# avr_gamepanel.net
KiCad netlist of a schematic drawn in EAGLE
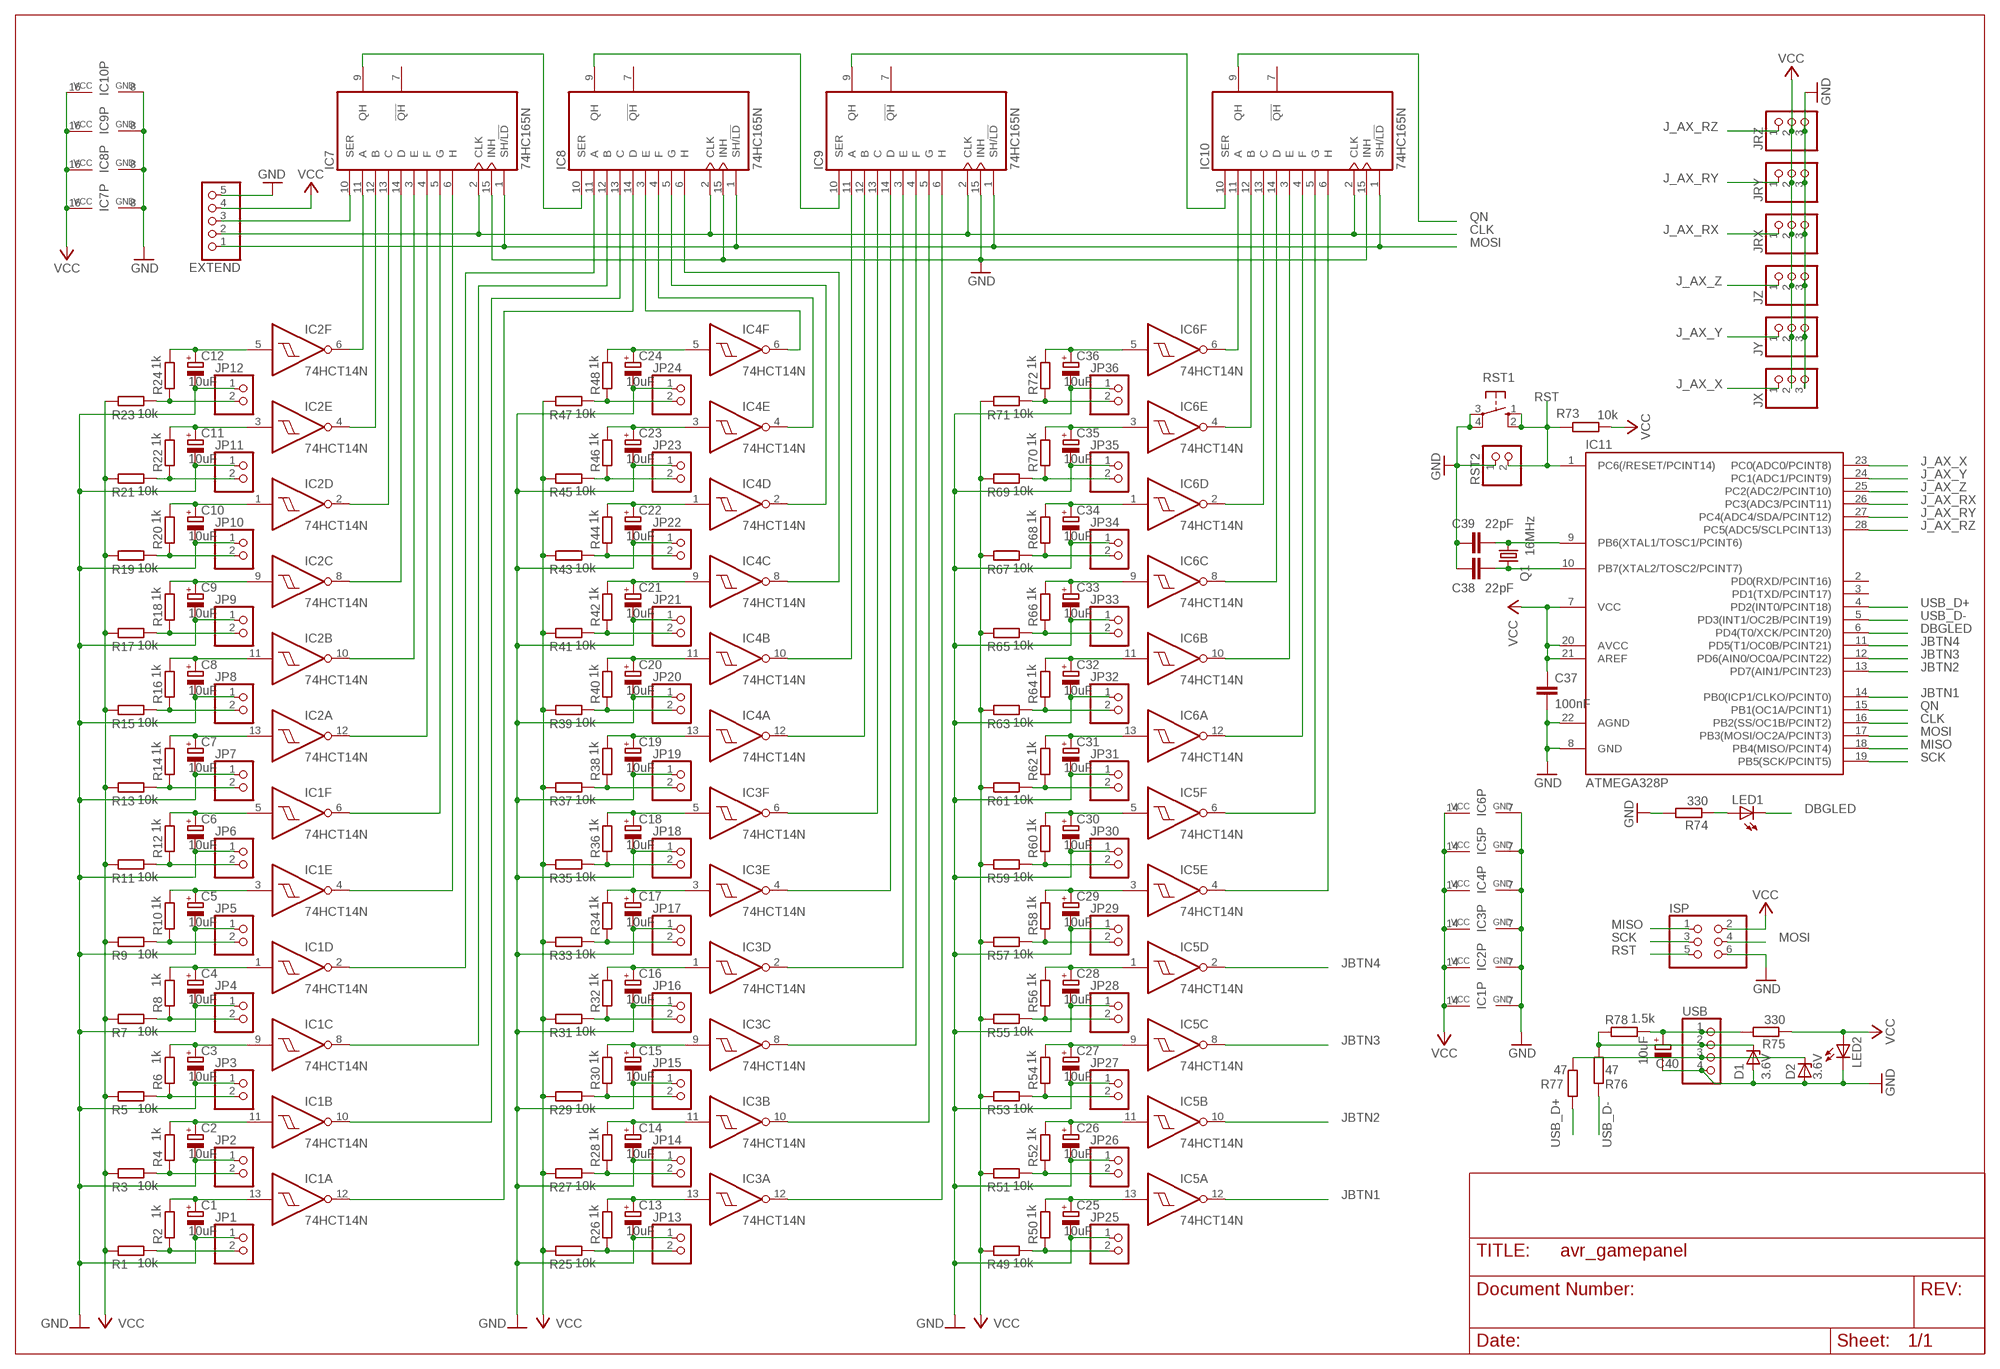
[diagram p0: schematic, sheet 1]

(export (version "E")
  (design (tool "Eeschema 10.0.6"))
  (components
    (comp (ref "C1")
      (value "10uF")
      (footprint "eagle-import:E2-5")
      (libsource (lib "eagle-import") (part "CPOL-EUE2-5"))
    )
    (comp (ref "C2")
      (value "10uF")
      (footprint "eagle-import:E2-5")
      (libsource (lib "eagle-import") (part "CPOL-EUE2-5"))
    )
    (comp (ref "C3")
      (value "10uF")
      (footprint "eagle-import:E2-5")
      (libsource (lib "eagle-import") (part "CPOL-EUE2-5"))
    )
    (comp (ref "C4")
      (value "10uF")
      (footprint "eagle-import:E2-5")
      (libsource (lib "eagle-import") (part "CPOL-EUE2-5"))
    )
    (comp (ref "C5")
      (value "10uF")
      (footprint "eagle-import:E2-5")
      (libsource (lib "eagle-import") (part "CPOL-EUE2-5"))
    )
    (comp (ref "C6")
      (value "10uF")
      (footprint "eagle-import:E2-5")
      (libsource (lib "eagle-import") (part "CPOL-EUE2-5"))
    )
    (comp (ref "C7")
      (value "10uF")
      (footprint "eagle-import:E2-5")
      (libsource (lib "eagle-import") (part "CPOL-EUE2-5"))
    )
    (comp (ref "C8")
      (value "10uF")
      (footprint "eagle-import:E2-5")
      (libsource (lib "eagle-import") (part "CPOL-EUE2-5"))
    )
    (comp (ref "C9")
      (value "10uF")
      (footprint "eagle-import:E2-5")
      (libsource (lib "eagle-import") (part "CPOL-EUE2-5"))
    )
    (comp (ref "C10")
      (value "10uF")
      (footprint "eagle-import:E2-5")
      (libsource (lib "eagle-import") (part "CPOL-EUE2-5"))
    )
    (comp (ref "C11")
      (value "10uF")
      (footprint "eagle-import:E2-5")
      (libsource (lib "eagle-import") (part "CPOL-EUE2-5"))
    )
    (comp (ref "C12")
      (value "10uF")
      (footprint "eagle-import:E2-5")
      (libsource (lib "eagle-import") (part "CPOL-EUE2-5"))
    )
    (comp (ref "C13")
      (value "10uF")
      (footprint "eagle-import:E2-5")
      (libsource (lib "eagle-import") (part "CPOL-EUE2-5"))
    )
    (comp (ref "C14")
      (value "10uF")
      (footprint "eagle-import:E2-5")
      (libsource (lib "eagle-import") (part "CPOL-EUE2-5"))
    )
    (comp (ref "C15")
      (value "10uF")
      (footprint "eagle-import:E2-5")
      (libsource (lib "eagle-import") (part "CPOL-EUE2-5"))
    )
    (comp (ref "C16")
      (value "10uF")
      (footprint "eagle-import:E2-5")
      (libsource (lib "eagle-import") (part "CPOL-EUE2-5"))
    )
    (comp (ref "C17")
      (value "10uF")
      (footprint "eagle-import:E2-5")
      (libsource (lib "eagle-import") (part "CPOL-EUE2-5"))
    )
    (comp (ref "C18")
      (value "10uF")
      (footprint "eagle-import:E2-5")
      (libsource (lib "eagle-import") (part "CPOL-EUE2-5"))
    )
    (comp (ref "C19")
      (value "10uF")
      (footprint "eagle-import:E2-5")
      (libsource (lib "eagle-import") (part "CPOL-EUE2-5"))
    )
    (comp (ref "C20")
      (value "10uF")
      (footprint "eagle-import:E2-5")
      (libsource (lib "eagle-import") (part "CPOL-EUE2-5"))
    )
    (comp (ref "C21")
      (value "10uF")
      (footprint "eagle-import:E2-5")
      (libsource (lib "eagle-import") (part "CPOL-EUE2-5"))
    )
    (comp (ref "C22")
      (value "10uF")
      (footprint "eagle-import:E2-5")
      (libsource (lib "eagle-import") (part "CPOL-EUE2-5"))
    )
    (comp (ref "C23")
      (value "10uF")
      (footprint "eagle-import:E2-5")
      (libsource (lib "eagle-import") (part "CPOL-EUE2-5"))
    )
    (comp (ref "C24")
      (value "10uF")
      (footprint "eagle-import:E2-5")
      (libsource (lib "eagle-import") (part "CPOL-EUE2-5"))
    )
    (comp (ref "C25")
      (value "10uF")
      (footprint "eagle-import:E2-5")
      (libsource (lib "eagle-import") (part "CPOL-EUE2-5"))
    )
    (comp (ref "C26")
      (value "10uF")
      (footprint "eagle-import:E2-5")
      (libsource (lib "eagle-import") (part "CPOL-EUE2-5"))
    )
    (comp (ref "C27")
      (value "10uF")
      (footprint "eagle-import:E2-5")
      (libsource (lib "eagle-import") (part "CPOL-EUE2-5"))
    )
    (comp (ref "C28")
      (value "10uF")
      (footprint "eagle-import:E2-5")
      (libsource (lib "eagle-import") (part "CPOL-EUE2-5"))
    )
    (comp (ref "C29")
      (value "10uF")
      (footprint "eagle-import:E2-5")
      (libsource (lib "eagle-import") (part "CPOL-EUE2-5"))
    )
    (comp (ref "C30")
      (value "10uF")
      (footprint "eagle-import:E2-5")
      (libsource (lib "eagle-import") (part "CPOL-EUE2-5"))
    )
    (comp (ref "C31")
      (value "10uF")
      (footprint "eagle-import:E2-5")
      (libsource (lib "eagle-import") (part "CPOL-EUE2-5"))
    )
    (comp (ref "C32")
      (value "10uF")
      (footprint "eagle-import:E2-5")
      (libsource (lib "eagle-import") (part "CPOL-EUE2-5"))
    )
    (comp (ref "C33")
      (value "10uF")
      (footprint "eagle-import:E2-5")
      (libsource (lib "eagle-import") (part "CPOL-EUE2-5"))
    )
    (comp (ref "C34")
      (value "10uF")
      (footprint "eagle-import:E2-5")
      (libsource (lib "eagle-import") (part "CPOL-EUE2-5"))
    )
    (comp (ref "C35")
      (value "10uF")
      (footprint "eagle-import:E2-5")
      (libsource (lib "eagle-import") (part "CPOL-EUE2-5"))
    )
    (comp (ref "C36")
      (value "10uF")
      (footprint "eagle-import:E2-5")
      (libsource (lib "eagle-import") (part "CPOL-EUE2-5"))
    )
    (comp (ref "C37")
      (value "100nF")
      (footprint "eagle-import:C025-024X044")
      (libsource (lib "eagle-import") (part "C-EU025-024X044"))
    )
    (comp (ref "C38")
      (value "22pF")
      (footprint "eagle-import:C025-024X044")
      (libsource (lib "eagle-import") (part "C-EU025-024X044"))
    )
    (comp (ref "C39")
      (value "22pF")
      (footprint "eagle-import:C025-024X044")
      (libsource (lib "eagle-import") (part "C-EU025-024X044"))
    )
    (comp (ref "C40")
      (value "10uF")
      (footprint "eagle-import:E2,5-6E")
      (libsource (lib "eagle-import") (part "CPOL-EUE2,5-6E"))
    )
    (comp (ref "D1")
      (value "3.6V")
      (footprint "eagle-import:ZDIO-2.5")
      (libsource (lib "eagle-import") (part "ZENER-DIODEZD-2.5"))
    )
    (comp (ref "D2")
      (value "3.6V")
      (footprint "eagle-import:ZDIO-2.5")
      (libsource (lib "eagle-import") (part "ZENER-DIODEZD-2.5"))
    )
    (comp (ref "EXTEND")
      (value "PINHD-1X5")
      (footprint "eagle-import:1X05")
      (libsource (lib "eagle-import") (part "PINHD-1X5"))
    )
    (comp (ref "IC1")
      (value "74HCT14N")
      (footprint "eagle-import:DIL14")
      (libsource (lib "eagle-import") (part "7414NHCT"))
    )
    (comp (ref "IC2")
      (value "74HCT14N")
      (footprint "eagle-import:DIL14")
      (libsource (lib "eagle-import") (part "7414NHCT"))
    )
    (comp (ref "IC3")
      (value "74HCT14N")
      (footprint "eagle-import:DIL14")
      (libsource (lib "eagle-import") (part "7414NHCT"))
    )
    (comp (ref "IC4")
      (value "74HCT14N")
      (footprint "eagle-import:DIL14")
      (libsource (lib "eagle-import") (part "7414NHCT"))
    )
    (comp (ref "IC5")
      (value "74HCT14N")
      (footprint "eagle-import:DIL14")
      (libsource (lib "eagle-import") (part "7414NHCT"))
    )
    (comp (ref "IC6")
      (value "74HCT14N")
      (footprint "eagle-import:DIL14")
      (libsource (lib "eagle-import") (part "7414NHCT"))
    )
    (comp (ref "IC7")
      (value "74HC165N")
      (footprint "eagle-import:DIL16")
      (libsource (lib "eagle-import") (part "74165NHC"))
    )
    (comp (ref "IC8")
      (value "74HC165N")
      (footprint "eagle-import:DIL16")
      (libsource (lib "eagle-import") (part "74165NHC"))
    )
    (comp (ref "IC9")
      (value "74HC165N")
      (footprint "eagle-import:DIL16")
      (libsource (lib "eagle-import") (part "74165NHC"))
    )
    (comp (ref "IC10")
      (value "74HC165N")
      (footprint "eagle-import:DIL16")
      (libsource (lib "eagle-import") (part "74165NHC"))
    )
    (comp (ref "IC11")
      (value "ATMEGA328P")
      (footprint "eagle-import:DIL28-3")
      (libsource (lib "eagle-import") (part "MEGA48/88/168-PU"))
    )
    (comp (ref "ISP")
      (value "PINHD-2X3")
      (footprint "eagle-import:2X03")
      (libsource (lib "eagle-import") (part "PINHD-2X3"))
    )
    (comp (ref "JP1")
      (value "PINHD-1X2")
      (footprint "eagle-import:1X02")
      (libsource (lib "eagle-import") (part "PINHD-1X2"))
    )
    (comp (ref "JP2")
      (value "PINHD-1X2")
      (footprint "eagle-import:1X02")
      (libsource (lib "eagle-import") (part "PINHD-1X2"))
    )
    (comp (ref "JP3")
      (value "PINHD-1X2")
      (footprint "eagle-import:1X02")
      (libsource (lib "eagle-import") (part "PINHD-1X2"))
    )
    (comp (ref "JP4")
      (value "PINHD-1X2")
      (footprint "eagle-import:1X02")
      (libsource (lib "eagle-import") (part "PINHD-1X2"))
    )
    (comp (ref "JP5")
      (value "PINHD-1X2")
      (footprint "eagle-import:1X02")
      (libsource (lib "eagle-import") (part "PINHD-1X2"))
    )
    (comp (ref "JP6")
      (value "PINHD-1X2")
      (footprint "eagle-import:1X02")
      (libsource (lib "eagle-import") (part "PINHD-1X2"))
    )
    (comp (ref "JP7")
      (value "PINHD-1X2")
      (footprint "eagle-import:1X02")
      (libsource (lib "eagle-import") (part "PINHD-1X2"))
    )
    (comp (ref "JP8")
      (value "PINHD-1X2")
      (footprint "eagle-import:1X02")
      (libsource (lib "eagle-import") (part "PINHD-1X2"))
    )
    (comp (ref "JP9")
      (value "PINHD-1X2")
      (footprint "eagle-import:1X02")
      (libsource (lib "eagle-import") (part "PINHD-1X2"))
    )
    (comp (ref "JP10")
      (value "PINHD-1X2")
      (footprint "eagle-import:1X02")
      (libsource (lib "eagle-import") (part "PINHD-1X2"))
    )
    (comp (ref "JP11")
      (value "PINHD-1X2")
      (footprint "eagle-import:1X02")
      (libsource (lib "eagle-import") (part "PINHD-1X2"))
    )
    (comp (ref "JP12")
      (value "PINHD-1X2")
      (footprint "eagle-import:1X02")
      (libsource (lib "eagle-import") (part "PINHD-1X2"))
    )
    (comp (ref "JP13")
      (value "PINHD-1X2")
      (footprint "eagle-import:1X02")
      (libsource (lib "eagle-import") (part "PINHD-1X2"))
    )
    (comp (ref "JP14")
      (value "PINHD-1X2")
      (footprint "eagle-import:1X02")
      (libsource (lib "eagle-import") (part "PINHD-1X2"))
    )
    (comp (ref "JP15")
      (value "PINHD-1X2")
      (footprint "eagle-import:1X02")
      (libsource (lib "eagle-import") (part "PINHD-1X2"))
    )
    (comp (ref "JP16")
      (value "PINHD-1X2")
      (footprint "eagle-import:1X02")
      (libsource (lib "eagle-import") (part "PINHD-1X2"))
    )
    (comp (ref "JP17")
      (value "PINHD-1X2")
      (footprint "eagle-import:1X02")
      (libsource (lib "eagle-import") (part "PINHD-1X2"))
    )
    (comp (ref "JP18")
      (value "PINHD-1X2")
      (footprint "eagle-import:1X02")
      (libsource (lib "eagle-import") (part "PINHD-1X2"))
    )
    (comp (ref "JP19")
      (value "PINHD-1X2")
      (footprint "eagle-import:1X02")
      (libsource (lib "eagle-import") (part "PINHD-1X2"))
    )
    (comp (ref "JP20")
      (value "PINHD-1X2")
      (footprint "eagle-import:1X02")
      (libsource (lib "eagle-import") (part "PINHD-1X2"))
    )
    (comp (ref "JP21")
      (value "PINHD-1X2")
      (footprint "eagle-import:1X02")
      (libsource (lib "eagle-import") (part "PINHD-1X2"))
    )
    (comp (ref "JP22")
      (value "PINHD-1X2")
      (footprint "eagle-import:1X02")
      (libsource (lib "eagle-import") (part "PINHD-1X2"))
    )
    (comp (ref "JP23")
      (value "PINHD-1X2")
      (footprint "eagle-import:1X02")
      (libsource (lib "eagle-import") (part "PINHD-1X2"))
    )
    (comp (ref "JP24")
      (value "PINHD-1X2")
      (footprint "eagle-import:1X02")
      (libsource (lib "eagle-import") (part "PINHD-1X2"))
    )
    (comp (ref "JP25")
      (value "PINHD-1X2")
      (footprint "eagle-import:1X02")
      (libsource (lib "eagle-import") (part "PINHD-1X2"))
    )
    (comp (ref "JP26")
      (value "PINHD-1X2")
      (footprint "eagle-import:1X02")
      (libsource (lib "eagle-import") (part "PINHD-1X2"))
    )
    (comp (ref "JP27")
      (value "PINHD-1X2")
      (footprint "eagle-import:1X02")
      (libsource (lib "eagle-import") (part "PINHD-1X2"))
    )
    (comp (ref "JP28")
      (value "PINHD-1X2")
      (footprint "eagle-import:1X02")
      (libsource (lib "eagle-import") (part "PINHD-1X2"))
    )
    (comp (ref "JP29")
      (value "PINHD-1X2")
      (footprint "eagle-import:1X02")
      (libsource (lib "eagle-import") (part "PINHD-1X2"))
    )
    (comp (ref "JP30")
      (value "PINHD-1X2")
      (footprint "eagle-import:1X02")
      (libsource (lib "eagle-import") (part "PINHD-1X2"))
    )
    (comp (ref "JP31")
      (value "PINHD-1X2")
      (footprint "eagle-import:1X02")
      (libsource (lib "eagle-import") (part "PINHD-1X2"))
    )
    (comp (ref "JP32")
      (value "PINHD-1X2")
      (footprint "eagle-import:1X02")
      (libsource (lib "eagle-import") (part "PINHD-1X2"))
    )
    (comp (ref "JP33")
      (value "PINHD-1X2")
      (footprint "eagle-import:1X02")
      (libsource (lib "eagle-import") (part "PINHD-1X2"))
    )
    (comp (ref "JP34")
      (value "PINHD-1X2")
      (footprint "eagle-import:1X02")
      (libsource (lib "eagle-import") (part "PINHD-1X2"))
    )
    (comp (ref "JP35")
      (value "PINHD-1X2")
      (footprint "eagle-import:1X02")
      (libsource (lib "eagle-import") (part "PINHD-1X2"))
    )
    (comp (ref "JP36")
      (value "PINHD-1X2")
      (footprint "eagle-import:1X02")
      (libsource (lib "eagle-import") (part "PINHD-1X2"))
    )
    (comp (ref "JRX")
      (value "PINHD-1X3")
      (footprint "eagle-import:1X03")
      (libsource (lib "eagle-import") (part "PINHD-1X3"))
    )
    (comp (ref "JRY")
      (value "PINHD-1X3")
      (footprint "eagle-import:1X03")
      (libsource (lib "eagle-import") (part "PINHD-1X3"))
    )
    (comp (ref "JRZ")
      (value "PINHD-1X3")
      (footprint "eagle-import:1X03")
      (libsource (lib "eagle-import") (part "PINHD-1X3"))
    )
    (comp (ref "JX")
      (value "PINHD-1X3")
      (footprint "eagle-import:1X03")
      (libsource (lib "eagle-import") (part "PINHD-1X3"))
    )
    (comp (ref "JY")
      (value "PINHD-1X3")
      (footprint "eagle-import:1X03")
      (libsource (lib "eagle-import") (part "PINHD-1X3"))
    )
    (comp (ref "JZ")
      (value "PINHD-1X3")
      (footprint "eagle-import:1X03")
      (libsource (lib "eagle-import") (part "PINHD-1X3"))
    )
    (comp (ref "LED1")
      (value "LEDLZR181")
      (footprint "eagle-import:LZR181")
      (libsource (lib "eagle-import") (part "LEDLZR181"))
    )
    (comp (ref "LED2")
      (value "LEDLZR181")
      (footprint "eagle-import:LZR181")
      (libsource (lib "eagle-import") (part "LEDLZR181"))
    )
    (comp (ref "Q1")
      (value "16MHz")
      (footprint "eagle-import:HC49_S")
      (libsource (lib "eagle-import") (part "CRYSTALHC49S"))
    )
    (comp (ref "R1")
      (value "10k")
      (footprint "eagle-import:0204V")
      (libsource (lib "eagle-import") (part "R-EU_0204/2V"))
    )
    (comp (ref "R2")
      (value "1k")
      (footprint "eagle-import:0204_5")
      (libsource (lib "eagle-import") (part "R-EU_0204/5"))
    )
    (comp (ref "R3")
      (value "10k")
      (footprint "eagle-import:0204V")
      (libsource (lib "eagle-import") (part "R-EU_0204/2V"))
    )
    (comp (ref "R4")
      (value "1k")
      (footprint "eagle-import:0204_5")
      (libsource (lib "eagle-import") (part "R-EU_0204/5"))
    )
    (comp (ref "R5")
      (value "10k")
      (footprint "eagle-import:0204V")
      (libsource (lib "eagle-import") (part "R-EU_0204/2V"))
    )
    (comp (ref "R6")
      (value "1k")
      (footprint "eagle-import:0204_5")
      (libsource (lib "eagle-import") (part "R-EU_0204/5"))
    )
    (comp (ref "R7")
      (value "10k")
      (footprint "eagle-import:0204V")
      (libsource (lib "eagle-import") (part "R-EU_0204/2V"))
    )
    (comp (ref "R8")
      (value "1k")
      (footprint "eagle-import:0204_5")
      (libsource (lib "eagle-import") (part "R-EU_0204/5"))
    )
    (comp (ref "R9")
      (value "10k")
      (footprint "eagle-import:0204V")
      (libsource (lib "eagle-import") (part "R-EU_0204/2V"))
    )
    (comp (ref "R10")
      (value "1k")
      (footprint "eagle-import:0204_5")
      (libsource (lib "eagle-import") (part "R-EU_0204/5"))
    )
    (comp (ref "R11")
      (value "10k")
      (footprint "eagle-import:0204V")
      (libsource (lib "eagle-import") (part "R-EU_0204/2V"))
    )
    (comp (ref "R12")
      (value "1k")
      (footprint "eagle-import:0204_5")
      (libsource (lib "eagle-import") (part "R-EU_0204/5"))
    )
    (comp (ref "R13")
      (value "10k")
      (footprint "eagle-import:0204V")
      (libsource (lib "eagle-import") (part "R-EU_0204/2V"))
    )
    (comp (ref "R14")
      (value "1k")
      (footprint "eagle-import:0204_5")
      (libsource (lib "eagle-import") (part "R-EU_0204/5"))
    )
    (comp (ref "R15")
      (value "10k")
      (footprint "eagle-import:0204V")
      (libsource (lib "eagle-import") (part "R-EU_0204/2V"))
    )
    (comp (ref "R16")
      (value "1k")
      (footprint "eagle-import:0204_5")
      (libsource (lib "eagle-import") (part "R-EU_0204/5"))
    )
    (comp (ref "R17")
      (value "10k")
      (footprint "eagle-import:0204V")
      (libsource (lib "eagle-import") (part "R-EU_0204/2V"))
    )
    (comp (ref "R18")
      (value "1k")
      (footprint "eagle-import:0204_5")
      (libsource (lib "eagle-import") (part "R-EU_0204/5"))
    )
    (comp (ref "R19")
      (value "10k")
      (footprint "eagle-import:0204V")
      (libsource (lib "eagle-import") (part "R-EU_0204/2V"))
    )
    (comp (ref "R20")
      (value "1k")
      (footprint "eagle-import:0204_5")
      (libsource (lib "eagle-import") (part "R-EU_0204/5"))
    )
    (comp (ref "R21")
      (value "10k")
      (footprint "eagle-import:0204V")
      (libsource (lib "eagle-import") (part "R-EU_0204/2V"))
    )
    (comp (ref "R22")
      (value "1k")
      (footprint "eagle-import:0204_5")
      (libsource (lib "eagle-import") (part "R-EU_0204/5"))
    )
    (comp (ref "R23")
      (value "10k")
      (footprint "eagle-import:0204V")
      (libsource (lib "eagle-import") (part "R-EU_0204/2V"))
    )
    (comp (ref "R24")
      (value "1k")
      (footprint "eagle-import:0204_5")
      (libsource (lib "eagle-import") (part "R-EU_0204/5"))
    )
    (comp (ref "R25")
      (value "10k")
      (footprint "eagle-import:0204V")
      (libsource (lib "eagle-import") (part "R-EU_0204/2V"))
    )
    (comp (ref "R26")
      (value "1k")
      (footprint "eagle-import:0204_5")
      (libsource (lib "eagle-import") (part "R-EU_0204/5"))
    )
    (comp (ref "R27")
      (value "10k")
      (footprint "eagle-import:0204V")
      (libsource (lib "eagle-import") (part "R-EU_0204/2V"))
    )
    (comp (ref "R28")
      (value "1k")
      (footprint "eagle-import:0204_5")
      (libsource (lib "eagle-import") (part "R-EU_0204/5"))
    )
    (comp (ref "R29")
      (value "10k")
      (footprint "eagle-import:0204V")
      (libsource (lib "eagle-import") (part "R-EU_0204/2V"))
    )
    (comp (ref "R30")
      (value "1k")
      (footprint "eagle-import:0204_5")
      (libsource (lib "eagle-import") (part "R-EU_0204/5"))
    )
    (comp (ref "R31")
      (value "10k")
      (footprint "eagle-import:0204V")
      (libsource (lib "eagle-import") (part "R-EU_0204/2V"))
    )
    (comp (ref "R32")
      (value "1k")
      (footprint "eagle-import:0204_5")
      (libsource (lib "eagle-import") (part "R-EU_0204/5"))
    )
    (comp (ref "R33")
      (value "10k")
      (footprint "eagle-import:0204V")
      (libsource (lib "eagle-import") (part "R-EU_0204/2V"))
    )
    (comp (ref "R34")
      (value "1k")
      (footprint "eagle-import:0204_5")
      (libsource (lib "eagle-import") (part "R-EU_0204/5"))
    )
    (comp (ref "R35")
      (value "10k")
      (footprint "eagle-import:0204V")
      (libsource (lib "eagle-import") (part "R-EU_0204/2V"))
    )
    (comp (ref "R36")
      (value "1k")
      (footprint "eagle-import:0204_5")
      (libsource (lib "eagle-import") (part "R-EU_0204/5"))
    )
    (comp (ref "R37")
      (value "10k")
      (footprint "eagle-import:0204V")
      (libsource (lib "eagle-import") (part "R-EU_0204/2V"))
    )
    (comp (ref "R38")
      (value "1k")
      (footprint "eagle-import:0204_5")
      (libsource (lib "eagle-import") (part "R-EU_0204/5"))
    )
    (comp (ref "R39")
      (value "10k")
      (footprint "eagle-import:0204V")
      (libsource (lib "eagle-import") (part "R-EU_0204/2V"))
    )
    (comp (ref "R40")
      (value "1k")
      (footprint "eagle-import:0204_5")
      (libsource (lib "eagle-import") (part "R-EU_0204/5"))
    )
    (comp (ref "R41")
      (value "10k")
      (footprint "eagle-import:0204V")
      (libsource (lib "eagle-import") (part "R-EU_0204/2V"))
    )
    (comp (ref "R42")
      (value "1k")
      (footprint "eagle-import:0204_5")
      (libsource (lib "eagle-import") (part "R-EU_0204/5"))
    )
    (comp (ref "R43")
      (value "10k")
      (footprint "eagle-import:0204V")
      (libsource (lib "eagle-import") (part "R-EU_0204/2V"))
    )
    (comp (ref "R44")
      (value "1k")
      (footprint "eagle-import:0204_5")
      (libsource (lib "eagle-import") (part "R-EU_0204/5"))
    )
    (comp (ref "R45")
      (value "10k")
      (footprint "eagle-import:0204V")
      (libsource (lib "eagle-import") (part "R-EU_0204/2V"))
    )
    (comp (ref "R46")
      (value "1k")
      (footprint "eagle-import:0204_5")
      (libsource (lib "eagle-import") (part "R-EU_0204/5"))
    )
    (comp (ref "R47")
      (value "10k")
      (footprint "eagle-import:0204V")
      (libsource (lib "eagle-import") (part "R-EU_0204/2V"))
    )
    (comp (ref "R48")
      (value "1k")
      (footprint "eagle-import:0204_5")
      (libsource (lib "eagle-import") (part "R-EU_0204/5"))
    )
    (comp (ref "R49")
      (value "10k")
      (footprint "eagle-import:0204V")
      (libsource (lib "eagle-import") (part "R-EU_0204/2V"))
    )
    (comp (ref "R50")
      (value "1k")
      (footprint "eagle-import:0204_5")
      (libsource (lib "eagle-import") (part "R-EU_0204/5"))
    )
    (comp (ref "R51")
      (value "10k")
      (footprint "eagle-import:0204V")
      (libsource (lib "eagle-import") (part "R-EU_0204/2V"))
    )
    (comp (ref "R52")
      (value "1k")
      (footprint "eagle-import:0204_5")
      (libsource (lib "eagle-import") (part "R-EU_0204/5"))
    )
    (comp (ref "R53")
      (value "10k")
      (footprint "eagle-import:0204V")
      (libsource (lib "eagle-import") (part "R-EU_0204/2V"))
    )
    (comp (ref "R54")
      (value "1k")
      (footprint "eagle-import:0204_5")
      (libsource (lib "eagle-import") (part "R-EU_0204/5"))
    )
    (comp (ref "R55")
      (value "10k")
      (footprint "eagle-import:0204V")
      (libsource (lib "eagle-import") (part "R-EU_0204/2V"))
    )
    (comp (ref "R56")
      (value "1k")
      (footprint "eagle-import:0204_5")
      (libsource (lib "eagle-import") (part "R-EU_0204/5"))
    )
    (comp (ref "R57")
      (value "10k")
      (footprint "eagle-import:0204V")
      (libsource (lib "eagle-import") (part "R-EU_0204/2V"))
    )
    (comp (ref "R58")
      (value "1k")
      (footprint "eagle-import:0204_5")
      (libsource (lib "eagle-import") (part "R-EU_0204/5"))
    )
    (comp (ref "R59")
      (value "10k")
      (footprint "eagle-import:0204V")
      (libsource (lib "eagle-import") (part "R-EU_0204/2V"))
    )
    (comp (ref "R60")
      (value "1k")
      (footprint "eagle-import:0204_5")
      (libsource (lib "eagle-import") (part "R-EU_0204/5"))
    )
    (comp (ref "R61")
      (value "10k")
      (footprint "eagle-import:0204V")
      (libsource (lib "eagle-import") (part "R-EU_0204/2V"))
    )
    (comp (ref "R62")
      (value "1k")
      (footprint "eagle-import:0204_5")
      (libsource (lib "eagle-import") (part "R-EU_0204/5"))
    )
    (comp (ref "R63")
      (value "10k")
      (footprint "eagle-import:0204V")
      (libsource (lib "eagle-import") (part "R-EU_0204/2V"))
    )
    (comp (ref "R64")
      (value "1k")
      (footprint "eagle-import:0204_5")
      (libsource (lib "eagle-import") (part "R-EU_0204/5"))
    )
    (comp (ref "R65")
      (value "10k")
      (footprint "eagle-import:0204V")
      (libsource (lib "eagle-import") (part "R-EU_0204/2V"))
    )
    (comp (ref "R66")
      (value "1k")
      (footprint "eagle-import:0204_5")
      (libsource (lib "eagle-import") (part "R-EU_0204/5"))
    )
    (comp (ref "R67")
      (value "10k")
      (footprint "eagle-import:0204V")
      (libsource (lib "eagle-import") (part "R-EU_0204/2V"))
    )
    (comp (ref "R68")
      (value "1k")
      (footprint "eagle-import:0204_5")
      (libsource (lib "eagle-import") (part "R-EU_0204/5"))
    )
    (comp (ref "R69")
      (value "10k")
      (footprint "eagle-import:0204V")
      (libsource (lib "eagle-import") (part "R-EU_0204/2V"))
    )
    (comp (ref "R70")
      (value "1k")
      (footprint "eagle-import:0204_5")
      (libsource (lib "eagle-import") (part "R-EU_0204/5"))
    )
    (comp (ref "R71")
      (value "10k")
      (footprint "eagle-import:0204V")
      (libsource (lib "eagle-import") (part "R-EU_0204/2V"))
    )
    (comp (ref "R72")
      (value "1k")
      (footprint "eagle-import:0204_5")
      (libsource (lib "eagle-import") (part "R-EU_0204/5"))
    )
    (comp (ref "R73")
      (value "10k")
      (footprint "eagle-import:0204_7")
      (libsource (lib "eagle-import") (part "R-EU_0204/7"))
    )
    (comp (ref "R74")
      (value "330")
      (footprint "eagle-import:0204_7")
      (libsource (lib "eagle-import") (part "R-EU_0204/7"))
    )
    (comp (ref "R75")
      (value "330")
      (footprint "eagle-import:0204_7")
      (libsource (lib "eagle-import") (part "R-EU_0204/7"))
    )
    (comp (ref "R76")
      (value "47")
      (footprint "eagle-import:0204_7")
      (libsource (lib "eagle-import") (part "R-EU_0204/7"))
    )
    (comp (ref "R77")
      (value "47")
      (footprint "eagle-import:0204_7")
      (libsource (lib "eagle-import") (part "R-EU_0204/7"))
    )
    (comp (ref "R78")
      (value "1.5k")
      (footprint "eagle-import:0204_7")
      (libsource (lib "eagle-import") (part "R-EU_0204/7"))
    )
    (comp (ref "RST1")
      (value "10-XX")
      (footprint "eagle-import:B3F-10XX")
      (fields (field (name "MPN") "B3F-1000"))
      (libsource (lib "eagle-import") (part "10-XX"))
    )
    (comp (ref "RST2")
      (value "PINHD-1X2")
      (footprint "eagle-import:1X02")
      (libsource (lib "eagle-import") (part "PINHD-1X2"))
    )
    (comp (ref "USB")
      (value "PINHD-1X4")
      (footprint "eagle-import:1X04")
      (libsource (lib "eagle-import") (part "PINHD-1X4"))
    )
  )
  (nets
    (net (code "1") (name "/CLK") (class "Default")
      (node (ref "EXTEND") (pin "2") (pinfunction "2_2") (pintype "passive"))
      (node (ref "IC10") (pin "2") (pinfunction "CLK_2") (pintype "input"))
      (node (ref "IC11") (pin "16") (pinfunction "PB2(SS/OC1B/PCINT2)_16") (pintype "bidirectional"))
      (node (ref "IC7") (pin "2") (pinfunction "CLK_2") (pintype "input"))
      (node (ref "IC8") (pin "2") (pinfunction "CLK_2") (pintype "input"))
      (node (ref "IC9") (pin "2") (pinfunction "CLK_2") (pintype "input"))
    )
    (net (code "2") (name "/DBGLED") (class "Default")
      (node (ref "IC11") (pin "6") (pinfunction "PD4(T0/XCK/PCINT20)_6") (pintype "bidirectional"))
      (node (ref "LED1") (pin "K") (pinfunction "C_K") (pintype "passive"))
    )
    (net (code "3") (name "/JBTN1") (class "Default")
      (node (ref "IC11") (pin "14") (pinfunction "PB0(ICP1/CLKO/PCINT0)_14") (pintype "bidirectional"))
      (node (ref "IC5") (pin "12") (pinfunction "O_12") (pintype "output"))
    )
    (net (code "4") (name "/JBTN2") (class "Default")
      (node (ref "IC11") (pin "13") (pinfunction "PD7(AIN1/PCINT23)_13") (pintype "bidirectional"))
      (node (ref "IC5") (pin "10") (pinfunction "O_10") (pintype "output"))
    )
    (net (code "5") (name "/JBTN3") (class "Default")
      (node (ref "IC11") (pin "12") (pinfunction "PD6(AIN0/OC0A/PCINT22)_12") (pintype "bidirectional"))
      (node (ref "IC5") (pin "8") (pinfunction "O_8") (pintype "output"))
    )
    (net (code "6") (name "/JBTN4") (class "Default")
      (node (ref "IC11") (pin "11") (pinfunction "PD5(T1/OC0B/PCINT21)_11") (pintype "bidirectional"))
      (node (ref "IC5") (pin "2") (pinfunction "O_2") (pintype "output"))
    )
    (net (code "7") (name "/J_AX_RX") (class "Default")
      (node (ref "IC11") (pin "26") (pinfunction "PC3(ADC3/PCINT11)_26") (pintype "bidirectional"))
      (node (ref "JRX") (pin "1") (pinfunction "1_1") (pintype "passive"))
    )
    (net (code "8") (name "/J_AX_RY") (class "Default")
      (node (ref "IC11") (pin "27") (pinfunction "PC4(ADC4/SDA/PCINT12)_27") (pintype "bidirectional"))
      (node (ref "JRY") (pin "1") (pinfunction "1_1") (pintype "passive"))
    )
    (net (code "9") (name "/J_AX_RZ") (class "Default")
      (node (ref "IC11") (pin "28") (pinfunction "PC5(ADC5/SCLPCINT13)_28") (pintype "bidirectional"))
      (node (ref "JRZ") (pin "1") (pinfunction "1_1") (pintype "passive"))
    )
    (net (code "10") (name "/J_AX_X") (class "Default")
      (node (ref "IC11") (pin "23") (pinfunction "PC0(ADC0/PCINT8)_23") (pintype "bidirectional"))
      (node (ref "JX") (pin "1") (pinfunction "1_1") (pintype "passive"))
    )
    (net (code "11") (name "/J_AX_Y") (class "Default")
      (node (ref "IC11") (pin "24") (pinfunction "PC1(ADC1/PCINT9)_24") (pintype "bidirectional"))
      (node (ref "JY") (pin "1") (pinfunction "1_1") (pintype "passive"))
    )
    (net (code "12") (name "/J_AX_Z") (class "Default")
      (node (ref "IC11") (pin "25") (pinfunction "PC2(ADC2/PCINT10)_25") (pintype "bidirectional"))
      (node (ref "JZ") (pin "1") (pinfunction "1_1") (pintype "passive"))
    )
    (net (code "13") (name "/MISO") (class "Default")
      (node (ref "IC11") (pin "18") (pinfunction "PB4(MISO/PCINT4)_18") (pintype "bidirectional"))
      (node (ref "ISP") (pin "1") (pinfunction "1_1") (pintype "passive"))
    )
    (net (code "14") (name "/MOSI") (class "Default")
      (node (ref "EXTEND") (pin "1") (pinfunction "1_1") (pintype "passive"))
      (node (ref "IC10") (pin "1") (pinfunction "SH/~{LD}_1") (pintype "input"))
      (node (ref "IC11") (pin "17") (pinfunction "PB3(MOSI/OC2A/PCINT3)_17") (pintype "bidirectional"))
      (node (ref "IC7") (pin "1") (pinfunction "SH/~{LD}_1") (pintype "input"))
      (node (ref "IC8") (pin "1") (pinfunction "SH/~{LD}_1") (pintype "input"))
      (node (ref "IC9") (pin "1") (pinfunction "SH/~{LD}_1") (pintype "input"))
      (node (ref "ISP") (pin "4") (pinfunction "4_4") (pintype "passive"))
    )
    (net (code "15") (name "/QN") (class "Default")
      (node (ref "IC10") (pin "9") (pinfunction "QH_9") (pintype "output"))
      (node (ref "IC11") (pin "15") (pinfunction "PB1(OC1A/PCINT1)_15") (pintype "bidirectional"))
    )
    (net (code "16") (name "/RST") (class "Default")
      (node (ref "IC11") (pin "1") (pinfunction "PC6(/RESET/PCINT14)_1") (pintype "bidirectional"))
      (node (ref "ISP") (pin "5") (pinfunction "5_5") (pintype "passive"))
      (node (ref "R73") (pin "2") (pinfunction "2_2") (pintype "passive"))
      (node (ref "RST1") (pin "1") (pinfunction "S_1") (pintype "passive"))
      (node (ref "RST1") (pin "2") (pinfunction "S1_2") (pintype "passive"))
      (node (ref "RST2") (pin "2") (pinfunction "2_2") (pintype "passive"))
    )
    (net (code "17") (name "/SCK") (class "Default")
      (node (ref "IC11") (pin "19") (pinfunction "PB5(SCK/PCINT5)_19") (pintype "bidirectional"))
      (node (ref "ISP") (pin "3") (pinfunction "3_3") (pintype "passive"))
    )
    (net (code "18") (name "/USB_D+") (class "Default")
      (node (ref "IC11") (pin "4") (pinfunction "PD2(INT0/PCINT18)_4") (pintype "bidirectional"))
      (node (ref "R77") (pin "2") (pinfunction "2_2") (pintype "passive"))
    )
    (net (code "19") (name "/USB_D-") (class "Default")
      (node (ref "IC11") (pin "5") (pinfunction "PD3(INT1/OC2B/PCINT19)_5") (pintype "bidirectional"))
      (node (ref "R76") (pin "2") (pinfunction "2_2") (pintype "passive"))
    )
    (net (code "20") (name "GND") (class "Default")
      (node (ref "C1") (pin "-") (pinfunction "-_-") (pintype "passive"))
      (node (ref "C10") (pin "-") (pinfunction "-_-") (pintype "passive"))
      (node (ref "C11") (pin "-") (pinfunction "-_-") (pintype "passive"))
      (node (ref "C12") (pin "-") (pinfunction "-_-") (pintype "passive"))
      (node (ref "C13") (pin "-") (pinfunction "-_-") (pintype "passive"))
      (node (ref "C14") (pin "-") (pinfunction "-_-") (pintype "passive"))
      (node (ref "C15") (pin "-") (pinfunction "-_-") (pintype "passive"))
      (node (ref "C16") (pin "-") (pinfunction "-_-") (pintype "passive"))
      (node (ref "C17") (pin "-") (pinfunction "-_-") (pintype "passive"))
      (node (ref "C18") (pin "-") (pinfunction "-_-") (pintype "passive"))
      (node (ref "C19") (pin "-") (pinfunction "-_-") (pintype "passive"))
      (node (ref "C2") (pin "-") (pinfunction "-_-") (pintype "passive"))
      (node (ref "C20") (pin "-") (pinfunction "-_-") (pintype "passive"))
      (node (ref "C21") (pin "-") (pinfunction "-_-") (pintype "passive"))
      (node (ref "C22") (pin "-") (pinfunction "-_-") (pintype "passive"))
      (node (ref "C23") (pin "-") (pinfunction "-_-") (pintype "passive"))
      (node (ref "C24") (pin "-") (pinfunction "-_-") (pintype "passive"))
      (node (ref "C25") (pin "-") (pinfunction "-_-") (pintype "passive"))
      (node (ref "C26") (pin "-") (pinfunction "-_-") (pintype "passive"))
      (node (ref "C27") (pin "-") (pinfunction "-_-") (pintype "passive"))
      (node (ref "C28") (pin "-") (pinfunction "-_-") (pintype "passive"))
      (node (ref "C29") (pin "-") (pinfunction "-_-") (pintype "passive"))
      (node (ref "C3") (pin "-") (pinfunction "-_-") (pintype "passive"))
      (node (ref "C30") (pin "-") (pinfunction "-_-") (pintype "passive"))
      (node (ref "C31") (pin "-") (pinfunction "-_-") (pintype "passive"))
      (node (ref "C32") (pin "-") (pinfunction "-_-") (pintype "passive"))
      (node (ref "C33") (pin "-") (pinfunction "-_-") (pintype "passive"))
      (node (ref "C34") (pin "-") (pinfunction "-_-") (pintype "passive"))
      (node (ref "C35") (pin "-") (pinfunction "-_-") (pintype "passive"))
      (node (ref "C36") (pin "-") (pinfunction "-_-") (pintype "passive"))
      (node (ref "C37") (pin "2") (pinfunction "2_2") (pintype "passive"))
      (node (ref "C38") (pin "1") (pinfunction "1_1") (pintype "passive"))
      (node (ref "C39") (pin "1") (pinfunction "1_1") (pintype "passive"))
      (node (ref "C4") (pin "-") (pinfunction "-_-") (pintype "passive"))
      (node (ref "C40") (pin "-") (pinfunction "-_-") (pintype "passive"))
      (node (ref "C5") (pin "-") (pinfunction "-_-") (pintype "passive"))
      (node (ref "C6") (pin "-") (pinfunction "-_-") (pintype "passive"))
      (node (ref "C7") (pin "-") (pinfunction "-_-") (pintype "passive"))
      (node (ref "C8") (pin "-") (pinfunction "-_-") (pintype "passive"))
      (node (ref "C9") (pin "-") (pinfunction "-_-") (pintype "passive"))
      (node (ref "D1") (pin "A") (pinfunction "A_A") (pintype "passive"))
      (node (ref "D2") (pin "A") (pinfunction "A_A") (pintype "passive"))
      (node (ref "EXTEND") (pin "5") (pinfunction "5_5") (pintype "passive"))
      (node (ref "IC1") (pin "7") (pinfunction "GND_7") (pintype "power_in"))
      (node (ref "IC10") (pin "15") (pinfunction "INH_15") (pintype "input"))
      (node (ref "IC10") (pin "8") (pinfunction "GND_8") (pintype "power_in"))
      (node (ref "IC11") (pin "22") (pinfunction "AGND_22") (pintype "power_in"))
      (node (ref "IC11") (pin "8") (pinfunction "GND_8") (pintype "power_in"))
      (node (ref "IC2") (pin "7") (pinfunction "GND_7") (pintype "power_in"))
      (node (ref "IC3") (pin "7") (pinfunction "GND_7") (pintype "power_in"))
      (node (ref "IC4") (pin "7") (pinfunction "GND_7") (pintype "power_in"))
      (node (ref "IC5") (pin "7") (pinfunction "GND_7") (pintype "power_in"))
      (node (ref "IC6") (pin "7") (pinfunction "GND_7") (pintype "power_in"))
      (node (ref "IC7") (pin "15") (pinfunction "INH_15") (pintype "input"))
      (node (ref "IC7") (pin "8") (pinfunction "GND_8") (pintype "power_in"))
      (node (ref "IC8") (pin "15") (pinfunction "INH_15") (pintype "input"))
      (node (ref "IC8") (pin "8") (pinfunction "GND_8") (pintype "power_in"))
      (node (ref "IC9") (pin "15") (pinfunction "INH_15") (pintype "input"))
      (node (ref "IC9") (pin "8") (pinfunction "GND_8") (pintype "power_in"))
      (node (ref "ISP") (pin "6") (pinfunction "6_6") (pintype "passive"))
      (node (ref "JP1") (pin "1") (pinfunction "1_1") (pintype "passive"))
      (node (ref "JP10") (pin "1") (pinfunction "1_1") (pintype "passive"))
      (node (ref "JP11") (pin "1") (pinfunction "1_1") (pintype "passive"))
      (node (ref "JP12") (pin "1") (pinfunction "1_1") (pintype "passive"))
      (node (ref "JP13") (pin "1") (pinfunction "1_1") (pintype "passive"))
      (node (ref "JP14") (pin "1") (pinfunction "1_1") (pintype "passive"))
      (node (ref "JP15") (pin "1") (pinfunction "1_1") (pintype "passive"))
      (node (ref "JP16") (pin "1") (pinfunction "1_1") (pintype "passive"))
      (node (ref "JP17") (pin "1") (pinfunction "1_1") (pintype "passive"))
      (node (ref "JP18") (pin "1") (pinfunction "1_1") (pintype "passive"))
      (node (ref "JP19") (pin "1") (pinfunction "1_1") (pintype "passive"))
      (node (ref "JP2") (pin "1") (pinfunction "1_1") (pintype "passive"))
      (node (ref "JP20") (pin "1") (pinfunction "1_1") (pintype "passive"))
      (node (ref "JP21") (pin "1") (pinfunction "1_1") (pintype "passive"))
      (node (ref "JP22") (pin "1") (pinfunction "1_1") (pintype "passive"))
      (node (ref "JP23") (pin "1") (pinfunction "1_1") (pintype "passive"))
      (node (ref "JP24") (pin "1") (pinfunction "1_1") (pintype "passive"))
      (node (ref "JP25") (pin "1") (pinfunction "1_1") (pintype "passive"))
      (node (ref "JP26") (pin "1") (pinfunction "1_1") (pintype "passive"))
      (node (ref "JP27") (pin "1") (pinfunction "1_1") (pintype "passive"))
      (node (ref "JP28") (pin "1") (pinfunction "1_1") (pintype "passive"))
      (node (ref "JP29") (pin "1") (pinfunction "1_1") (pintype "passive"))
      (node (ref "JP3") (pin "1") (pinfunction "1_1") (pintype "passive"))
      (node (ref "JP30") (pin "1") (pinfunction "1_1") (pintype "passive"))
      (node (ref "JP31") (pin "1") (pinfunction "1_1") (pintype "passive"))
      (node (ref "JP32") (pin "1") (pinfunction "1_1") (pintype "passive"))
      (node (ref "JP33") (pin "1") (pinfunction "1_1") (pintype "passive"))
      (node (ref "JP34") (pin "1") (pinfunction "1_1") (pintype "passive"))
      (node (ref "JP35") (pin "1") (pinfunction "1_1") (pintype "passive"))
      (node (ref "JP36") (pin "1") (pinfunction "1_1") (pintype "passive"))
      (node (ref "JP4") (pin "1") (pinfunction "1_1") (pintype "passive"))
      (node (ref "JP5") (pin "1") (pinfunction "1_1") (pintype "passive"))
      (node (ref "JP6") (pin "1") (pinfunction "1_1") (pintype "passive"))
      (node (ref "JP7") (pin "1") (pinfunction "1_1") (pintype "passive"))
      (node (ref "JP8") (pin "1") (pinfunction "1_1") (pintype "passive"))
      (node (ref "JP9") (pin "1") (pinfunction "1_1") (pintype "passive"))
      (node (ref "JRX") (pin "3") (pinfunction "3_3") (pintype "passive"))
      (node (ref "JRY") (pin "3") (pinfunction "3_3") (pintype "passive"))
      (node (ref "JRZ") (pin "3") (pinfunction "3_3") (pintype "passive"))
      (node (ref "JX") (pin "3") (pinfunction "3_3") (pintype "passive"))
      (node (ref "JY") (pin "3") (pinfunction "3_3") (pintype "passive"))
      (node (ref "JZ") (pin "3") (pinfunction "3_3") (pintype "passive"))
      (node (ref "LED2") (pin "K") (pinfunction "C_K") (pintype "passive"))
      (node (ref "R74") (pin "2") (pinfunction "2_2") (pintype "passive"))
      (node (ref "RST1") (pin "3") (pinfunction "P_3") (pintype "passive"))
      (node (ref "RST1") (pin "4") (pinfunction "P1_4") (pintype "passive"))
      (node (ref "RST2") (pin "1") (pinfunction "1_1") (pintype "passive"))
      (node (ref "USB") (pin "4") (pinfunction "4_4") (pintype "passive"))
    )
    (net (code "21") (name "Net-(C40-Pad+)") (class "Default")
      (node (ref "C40") (pin "+") (pinfunction "+_+") (pintype "passive"))
      (node (ref "R75") (pin "2") (pinfunction "2_2") (pintype "passive"))
      (node (ref "R78") (pin "2") (pinfunction "2_2") (pintype "passive"))
      (node (ref "USB") (pin "1") (pinfunction "1_1") (pintype "passive"))
    )
    (net (code "22") (name "Net-(D1-PadC)") (class "Default")
      (node (ref "D1") (pin "C") (pinfunction "C_C") (pintype "passive"))
      (node (ref "R76") (pin "1") (pinfunction "1_1") (pintype "passive"))
      (node (ref "R78") (pin "1") (pinfunction "1_1") (pintype "passive"))
      (node (ref "USB") (pin "2") (pinfunction "2_2") (pintype "passive"))
    )
    (net (code "23") (name "Net-(D2-PadC)") (class "Default")
      (node (ref "D2") (pin "C") (pinfunction "C_C") (pintype "passive"))
      (node (ref "R77") (pin "1") (pinfunction "1_1") (pintype "passive"))
      (node (ref "USB") (pin "3") (pinfunction "3_3") (pintype "passive"))
    )
    (net (code "24") (name "Net-(IC1A-I)") (class "Default")
      (node (ref "C1") (pin "+") (pinfunction "+_+") (pintype "passive"))
      (node (ref "IC1") (pin "13") (pinfunction "I_13") (pintype "input"))
      (node (ref "R2") (pin "2") (pinfunction "2_2") (pintype "passive"))
    )
    (net (code "25") (name "Net-(IC1A-O)") (class "Default")
      (node (ref "IC1") (pin "12") (pinfunction "O_12") (pintype "output"))
      (node (ref "IC8") (pin "14") (pinfunction "D_14") (pintype "input"))
    )
    (net (code "26") (name "Net-(IC1B-I)") (class "Default")
      (node (ref "C2") (pin "+") (pinfunction "+_+") (pintype "passive"))
      (node (ref "IC1") (pin "11") (pinfunction "I_11") (pintype "input"))
      (node (ref "R4") (pin "2") (pinfunction "2_2") (pintype "passive"))
    )
    (net (code "27") (name "Net-(IC1B-O)") (class "Default")
      (node (ref "IC1") (pin "10") (pinfunction "O_10") (pintype "output"))
      (node (ref "IC8") (pin "13") (pinfunction "C_13") (pintype "input"))
    )
    (net (code "28") (name "Net-(IC1C-I)") (class "Default")
      (node (ref "C3") (pin "+") (pinfunction "+_+") (pintype "passive"))
      (node (ref "IC1") (pin "9") (pinfunction "I_9") (pintype "input"))
      (node (ref "R6") (pin "2") (pinfunction "2_2") (pintype "passive"))
    )
    (net (code "29") (name "Net-(IC1C-O)") (class "Default")
      (node (ref "IC1") (pin "8") (pinfunction "O_8") (pintype "output"))
      (node (ref "IC8") (pin "12") (pinfunction "B_12") (pintype "input"))
    )
    (net (code "30") (name "Net-(IC1D-I)") (class "Default")
      (node (ref "C4") (pin "+") (pinfunction "+_+") (pintype "passive"))
      (node (ref "IC1") (pin "1") (pinfunction "I_1") (pintype "input"))
      (node (ref "R8") (pin "2") (pinfunction "2_2") (pintype "passive"))
    )
    (net (code "31") (name "Net-(IC1D-O)") (class "Default")
      (node (ref "IC1") (pin "2") (pinfunction "O_2") (pintype "output"))
      (node (ref "IC8") (pin "11") (pinfunction "A_11") (pintype "input"))
    )
    (net (code "32") (name "Net-(IC1E-I)") (class "Default")
      (node (ref "C5") (pin "+") (pinfunction "+_+") (pintype "passive"))
      (node (ref "IC1") (pin "3") (pinfunction "I_3") (pintype "input"))
      (node (ref "R10") (pin "2") (pinfunction "2_2") (pintype "passive"))
    )
    (net (code "33") (name "Net-(IC1E-O)") (class "Default")
      (node (ref "IC1") (pin "4") (pinfunction "O_4") (pintype "output"))
      (node (ref "IC7") (pin "6") (pinfunction "H_6") (pintype "input"))
    )
    (net (code "34") (name "Net-(IC1F-I)") (class "Default")
      (node (ref "C6") (pin "+") (pinfunction "+_+") (pintype "passive"))
      (node (ref "IC1") (pin "5") (pinfunction "I_5") (pintype "input"))
      (node (ref "R12") (pin "2") (pinfunction "2_2") (pintype "passive"))
    )
    (net (code "35") (name "Net-(IC1F-O)") (class "Default")
      (node (ref "IC1") (pin "6") (pinfunction "O_6") (pintype "output"))
      (node (ref "IC7") (pin "5") (pinfunction "G_5") (pintype "input"))
    )
    (net (code "36") (name "Net-(IC2A-I)") (class "Default")
      (node (ref "C7") (pin "+") (pinfunction "+_+") (pintype "passive"))
      (node (ref "IC2") (pin "13") (pinfunction "I_13") (pintype "input"))
      (node (ref "R14") (pin "2") (pinfunction "2_2") (pintype "passive"))
    )
    (net (code "37") (name "Net-(IC2A-O)") (class "Default")
      (node (ref "IC2") (pin "12") (pinfunction "O_12") (pintype "output"))
      (node (ref "IC7") (pin "4") (pinfunction "F_4") (pintype "input"))
    )
    (net (code "38") (name "Net-(IC2B-I)") (class "Default")
      (node (ref "C8") (pin "+") (pinfunction "+_+") (pintype "passive"))
      (node (ref "IC2") (pin "11") (pinfunction "I_11") (pintype "input"))
      (node (ref "R16") (pin "2") (pinfunction "2_2") (pintype "passive"))
    )
    (net (code "39") (name "Net-(IC2B-O)") (class "Default")
      (node (ref "IC2") (pin "10") (pinfunction "O_10") (pintype "output"))
      (node (ref "IC7") (pin "3") (pinfunction "E_3") (pintype "input"))
    )
    (net (code "40") (name "Net-(IC2C-I)") (class "Default")
      (node (ref "C9") (pin "+") (pinfunction "+_+") (pintype "passive"))
      (node (ref "IC2") (pin "9") (pinfunction "I_9") (pintype "input"))
      (node (ref "R18") (pin "2") (pinfunction "2_2") (pintype "passive"))
    )
    (net (code "41") (name "Net-(IC2C-O)") (class "Default")
      (node (ref "IC2") (pin "8") (pinfunction "O_8") (pintype "output"))
      (node (ref "IC7") (pin "14") (pinfunction "D_14") (pintype "input"))
    )
    (net (code "42") (name "Net-(IC2D-I)") (class "Default")
      (node (ref "C10") (pin "+") (pinfunction "+_+") (pintype "passive"))
      (node (ref "IC2") (pin "1") (pinfunction "I_1") (pintype "input"))
      (node (ref "R20") (pin "2") (pinfunction "2_2") (pintype "passive"))
    )
    (net (code "43") (name "Net-(IC2D-O)") (class "Default")
      (node (ref "IC2") (pin "2") (pinfunction "O_2") (pintype "output"))
      (node (ref "IC7") (pin "13") (pinfunction "C_13") (pintype "input"))
    )
    (net (code "44") (name "Net-(IC2E-I)") (class "Default")
      (node (ref "C11") (pin "+") (pinfunction "+_+") (pintype "passive"))
      (node (ref "IC2") (pin "3") (pinfunction "I_3") (pintype "input"))
      (node (ref "R22") (pin "2") (pinfunction "2_2") (pintype "passive"))
    )
    (net (code "45") (name "Net-(IC2E-O)") (class "Default")
      (node (ref "IC2") (pin "4") (pinfunction "O_4") (pintype "output"))
      (node (ref "IC7") (pin "12") (pinfunction "B_12") (pintype "input"))
    )
    (net (code "46") (name "Net-(IC2F-I)") (class "Default")
      (node (ref "C12") (pin "+") (pinfunction "+_+") (pintype "passive"))
      (node (ref "IC2") (pin "5") (pinfunction "I_5") (pintype "input"))
      (node (ref "R24") (pin "2") (pinfunction "2_2") (pintype "passive"))
    )
    (net (code "47") (name "Net-(IC2F-O)") (class "Default")
      (node (ref "IC2") (pin "6") (pinfunction "O_6") (pintype "output"))
      (node (ref "IC7") (pin "11") (pinfunction "A_11") (pintype "input"))
    )
    (net (code "48") (name "Net-(IC3A-I)") (class "Default")
      (node (ref "C13") (pin "+") (pinfunction "+_+") (pintype "passive"))
      (node (ref "IC3") (pin "13") (pinfunction "I_13") (pintype "input"))
      (node (ref "R26") (pin "2") (pinfunction "2_2") (pintype "passive"))
    )
    (net (code "49") (name "Net-(IC3A-O)") (class "Default")
      (node (ref "IC3") (pin "12") (pinfunction "O_12") (pintype "output"))
      (node (ref "IC9") (pin "6") (pinfunction "H_6") (pintype "input"))
    )
    (net (code "50") (name "Net-(IC3B-I)") (class "Default")
      (node (ref "C14") (pin "+") (pinfunction "+_+") (pintype "passive"))
      (node (ref "IC3") (pin "11") (pinfunction "I_11") (pintype "input"))
      (node (ref "R28") (pin "2") (pinfunction "2_2") (pintype "passive"))
    )
    (net (code "51") (name "Net-(IC3B-O)") (class "Default")
      (node (ref "IC3") (pin "10") (pinfunction "O_10") (pintype "output"))
      (node (ref "IC9") (pin "5") (pinfunction "G_5") (pintype "input"))
    )
    (net (code "52") (name "Net-(IC3C-I)") (class "Default")
      (node (ref "C15") (pin "+") (pinfunction "+_+") (pintype "passive"))
      (node (ref "IC3") (pin "9") (pinfunction "I_9") (pintype "input"))
      (node (ref "R30") (pin "2") (pinfunction "2_2") (pintype "passive"))
    )
    (net (code "53") (name "Net-(IC3C-O)") (class "Default")
      (node (ref "IC3") (pin "8") (pinfunction "O_8") (pintype "output"))
      (node (ref "IC9") (pin "4") (pinfunction "F_4") (pintype "input"))
    )
    (net (code "54") (name "Net-(IC3D-I)") (class "Default")
      (node (ref "C16") (pin "+") (pinfunction "+_+") (pintype "passive"))
      (node (ref "IC3") (pin "1") (pinfunction "I_1") (pintype "input"))
      (node (ref "R32") (pin "2") (pinfunction "2_2") (pintype "passive"))
    )
    (net (code "55") (name "Net-(IC3D-O)") (class "Default")
      (node (ref "IC3") (pin "2") (pinfunction "O_2") (pintype "output"))
      (node (ref "IC9") (pin "3") (pinfunction "E_3") (pintype "input"))
    )
    (net (code "56") (name "Net-(IC3E-I)") (class "Default")
      (node (ref "C17") (pin "+") (pinfunction "+_+") (pintype "passive"))
      (node (ref "IC3") (pin "3") (pinfunction "I_3") (pintype "input"))
      (node (ref "R34") (pin "2") (pinfunction "2_2") (pintype "passive"))
    )
    (net (code "57") (name "Net-(IC3E-O)") (class "Default")
      (node (ref "IC3") (pin "4") (pinfunction "O_4") (pintype "output"))
      (node (ref "IC9") (pin "14") (pinfunction "D_14") (pintype "input"))
    )
    (net (code "58") (name "Net-(IC3F-I)") (class "Default")
      (node (ref "C18") (pin "+") (pinfunction "+_+") (pintype "passive"))
      (node (ref "IC3") (pin "5") (pinfunction "I_5") (pintype "input"))
      (node (ref "R36") (pin "2") (pinfunction "2_2") (pintype "passive"))
    )
    (net (code "59") (name "Net-(IC3F-O)") (class "Default")
      (node (ref "IC3") (pin "6") (pinfunction "O_6") (pintype "output"))
      (node (ref "IC9") (pin "13") (pinfunction "C_13") (pintype "input"))
    )
    (net (code "60") (name "Net-(IC4A-I)") (class "Default")
      (node (ref "C19") (pin "+") (pinfunction "+_+") (pintype "passive"))
      (node (ref "IC4") (pin "13") (pinfunction "I_13") (pintype "input"))
      (node (ref "R38") (pin "2") (pinfunction "2_2") (pintype "passive"))
    )
    (net (code "61") (name "Net-(IC4A-O)") (class "Default")
      (node (ref "IC4") (pin "12") (pinfunction "O_12") (pintype "output"))
      (node (ref "IC9") (pin "12") (pinfunction "B_12") (pintype "input"))
    )
    (net (code "62") (name "Net-(IC4B-I)") (class "Default")
      (node (ref "C20") (pin "+") (pinfunction "+_+") (pintype "passive"))
      (node (ref "IC4") (pin "11") (pinfunction "I_11") (pintype "input"))
      (node (ref "R40") (pin "2") (pinfunction "2_2") (pintype "passive"))
    )
    (net (code "63") (name "Net-(IC4B-O)") (class "Default")
      (node (ref "IC4") (pin "10") (pinfunction "O_10") (pintype "output"))
      (node (ref "IC9") (pin "11") (pinfunction "A_11") (pintype "input"))
    )
    (net (code "64") (name "Net-(IC4C-I)") (class "Default")
      (node (ref "C21") (pin "+") (pinfunction "+_+") (pintype "passive"))
      (node (ref "IC4") (pin "9") (pinfunction "I_9") (pintype "input"))
      (node (ref "R42") (pin "2") (pinfunction "2_2") (pintype "passive"))
    )
    (net (code "65") (name "Net-(IC4C-O)") (class "Default")
      (node (ref "IC4") (pin "8") (pinfunction "O_8") (pintype "output"))
      (node (ref "IC8") (pin "6") (pinfunction "H_6") (pintype "input"))
    )
    (net (code "66") (name "Net-(IC4D-I)") (class "Default")
      (node (ref "C22") (pin "+") (pinfunction "+_+") (pintype "passive"))
      (node (ref "IC4") (pin "1") (pinfunction "I_1") (pintype "input"))
      (node (ref "R44") (pin "2") (pinfunction "2_2") (pintype "passive"))
    )
    (net (code "67") (name "Net-(IC4D-O)") (class "Default")
      (node (ref "IC4") (pin "2") (pinfunction "O_2") (pintype "output"))
      (node (ref "IC8") (pin "5") (pinfunction "G_5") (pintype "input"))
    )
    (net (code "68") (name "Net-(IC4E-I)") (class "Default")
      (node (ref "C23") (pin "+") (pinfunction "+_+") (pintype "passive"))
      (node (ref "IC4") (pin "3") (pinfunction "I_3") (pintype "input"))
      (node (ref "R46") (pin "2") (pinfunction "2_2") (pintype "passive"))
    )
    (net (code "69") (name "Net-(IC4E-O)") (class "Default")
      (node (ref "IC4") (pin "4") (pinfunction "O_4") (pintype "output"))
      (node (ref "IC8") (pin "4") (pinfunction "F_4") (pintype "input"))
    )
    (net (code "70") (name "Net-(IC4F-I)") (class "Default")
      (node (ref "C24") (pin "+") (pinfunction "+_+") (pintype "passive"))
      (node (ref "IC4") (pin "5") (pinfunction "I_5") (pintype "input"))
      (node (ref "R48") (pin "2") (pinfunction "2_2") (pintype "passive"))
    )
    (net (code "71") (name "Net-(IC4F-O)") (class "Default")
      (node (ref "IC4") (pin "6") (pinfunction "O_6") (pintype "output"))
      (node (ref "IC8") (pin "3") (pinfunction "E_3") (pintype "input"))
    )
    (net (code "72") (name "Net-(IC5A-I)") (class "Default")
      (node (ref "C25") (pin "+") (pinfunction "+_+") (pintype "passive"))
      (node (ref "IC5") (pin "13") (pinfunction "I_13") (pintype "input"))
      (node (ref "R50") (pin "2") (pinfunction "2_2") (pintype "passive"))
    )
    (net (code "73") (name "Net-(IC5B-I)") (class "Default")
      (node (ref "C26") (pin "+") (pinfunction "+_+") (pintype "passive"))
      (node (ref "IC5") (pin "11") (pinfunction "I_11") (pintype "input"))
      (node (ref "R52") (pin "2") (pinfunction "2_2") (pintype "passive"))
    )
    (net (code "74") (name "Net-(IC5C-I)") (class "Default")
      (node (ref "C27") (pin "+") (pinfunction "+_+") (pintype "passive"))
      (node (ref "IC5") (pin "9") (pinfunction "I_9") (pintype "input"))
      (node (ref "R54") (pin "2") (pinfunction "2_2") (pintype "passive"))
    )
    (net (code "75") (name "Net-(IC5D-I)") (class "Default")
      (node (ref "C28") (pin "+") (pinfunction "+_+") (pintype "passive"))
      (node (ref "IC5") (pin "1") (pinfunction "I_1") (pintype "input"))
      (node (ref "R56") (pin "2") (pinfunction "2_2") (pintype "passive"))
    )
    (net (code "76") (name "Net-(IC5E-I)") (class "Default")
      (node (ref "C29") (pin "+") (pinfunction "+_+") (pintype "passive"))
      (node (ref "IC5") (pin "3") (pinfunction "I_3") (pintype "input"))
      (node (ref "R58") (pin "2") (pinfunction "2_2") (pintype "passive"))
    )
    (net (code "77") (name "Net-(IC5F-I)") (class "Default")
      (node (ref "C30") (pin "+") (pinfunction "+_+") (pintype "passive"))
      (node (ref "IC5") (pin "5") (pinfunction "I_5") (pintype "input"))
      (node (ref "R60") (pin "2") (pinfunction "2_2") (pintype "passive"))
    )
    (net (code "78") (name "Net-(IC6A-I)") (class "Default")
      (node (ref "C31") (pin "+") (pinfunction "+_+") (pintype "passive"))
      (node (ref "IC6") (pin "13") (pinfunction "I_13") (pintype "input"))
      (node (ref "R62") (pin "2") (pinfunction "2_2") (pintype "passive"))
    )
    (net (code "79") (name "Net-(IC6B-I)") (class "Default")
      (node (ref "C32") (pin "+") (pinfunction "+_+") (pintype "passive"))
      (node (ref "IC6") (pin "11") (pinfunction "I_11") (pintype "input"))
      (node (ref "R64") (pin "2") (pinfunction "2_2") (pintype "passive"))
    )
    (net (code "80") (name "Net-(IC6C-I)") (class "Default")
      (node (ref "C33") (pin "+") (pinfunction "+_+") (pintype "passive"))
      (node (ref "IC6") (pin "9") (pinfunction "I_9") (pintype "input"))
      (node (ref "R66") (pin "2") (pinfunction "2_2") (pintype "passive"))
    )
    (net (code "81") (name "Net-(IC6D-I)") (class "Default")
      (node (ref "C34") (pin "+") (pinfunction "+_+") (pintype "passive"))
      (node (ref "IC6") (pin "1") (pinfunction "I_1") (pintype "input"))
      (node (ref "R68") (pin "2") (pinfunction "2_2") (pintype "passive"))
    )
    (net (code "82") (name "Net-(IC6E-I)") (class "Default")
      (node (ref "C35") (pin "+") (pinfunction "+_+") (pintype "passive"))
      (node (ref "IC6") (pin "3") (pinfunction "I_3") (pintype "input"))
      (node (ref "R70") (pin "2") (pinfunction "2_2") (pintype "passive"))
    )
    (net (code "83") (name "Net-(IC6F-I)") (class "Default")
      (node (ref "C36") (pin "+") (pinfunction "+_+") (pintype "passive"))
      (node (ref "IC6") (pin "5") (pinfunction "I_5") (pintype "input"))
      (node (ref "R72") (pin "2") (pinfunction "2_2") (pintype "passive"))
    )
    (net (code "84") (name "Net-(IC7A-QH)") (class "Default")
      (node (ref "IC7") (pin "9") (pinfunction "QH_9") (pintype "output"))
      (node (ref "IC8") (pin "10") (pinfunction "SER_10") (pintype "input"))
    )
    (net (code "85") (name "Net-(IC7A-SER)") (class "Default")
      (node (ref "EXTEND") (pin "3") (pinfunction "3_3") (pintype "passive"))
      (node (ref "IC7") (pin "10") (pinfunction "SER_10") (pintype "input"))
    )
    (net (code "86") (name "Net-(IC8A-QH)") (class "Default")
      (node (ref "IC8") (pin "9") (pinfunction "QH_9") (pintype "output"))
      (node (ref "IC9") (pin "10") (pinfunction "SER_10") (pintype "input"))
    )
    (net (code "87") (name "Net-(IC10A-A)") (class "Default")
      (node (ref "IC10") (pin "11") (pinfunction "A_11") (pintype "input"))
      (node (ref "IC6") (pin "6") (pinfunction "O_6") (pintype "output"))
    )
    (net (code "88") (name "Net-(IC10A-B)") (class "Default")
      (node (ref "IC10") (pin "12") (pinfunction "B_12") (pintype "input"))
      (node (ref "IC6") (pin "4") (pinfunction "O_4") (pintype "output"))
    )
    (net (code "89") (name "Net-(IC10A-C)") (class "Default")
      (node (ref "IC10") (pin "13") (pinfunction "C_13") (pintype "input"))
      (node (ref "IC6") (pin "2") (pinfunction "O_2") (pintype "output"))
    )
    (net (code "90") (name "Net-(IC10A-D)") (class "Default")
      (node (ref "IC10") (pin "14") (pinfunction "D_14") (pintype "input"))
      (node (ref "IC6") (pin "8") (pinfunction "O_8") (pintype "output"))
    )
    (net (code "91") (name "Net-(IC10A-E)") (class "Default")
      (node (ref "IC10") (pin "3") (pinfunction "E_3") (pintype "input"))
      (node (ref "IC6") (pin "10") (pinfunction "O_10") (pintype "output"))
    )
    (net (code "92") (name "Net-(IC10A-F)") (class "Default")
      (node (ref "IC10") (pin "4") (pinfunction "F_4") (pintype "input"))
      (node (ref "IC6") (pin "12") (pinfunction "O_12") (pintype "output"))
    )
    (net (code "93") (name "Net-(IC10A-G)") (class "Default")
      (node (ref "IC10") (pin "5") (pinfunction "G_5") (pintype "input"))
      (node (ref "IC5") (pin "6") (pinfunction "O_6") (pintype "output"))
    )
    (net (code "94") (name "Net-(IC10A-H)") (class "Default")
      (node (ref "IC10") (pin "6") (pinfunction "H_6") (pintype "input"))
      (node (ref "IC5") (pin "4") (pinfunction "O_4") (pintype "output"))
    )
    (net (code "95") (name "Net-(IC10A-SER)") (class "Default")
      (node (ref "IC10") (pin "10") (pinfunction "SER_10") (pintype "input"))
      (node (ref "IC9") (pin "9") (pinfunction "QH_9") (pintype "output"))
    )
    (net (code "96") (name "Net-(IC11-PB6(XTAL1{slash}TOSC1{slash}PCINT6))") (class "Default")
      (node (ref "C39") (pin "2") (pinfunction "2_2") (pintype "passive"))
      (node (ref "IC11") (pin "9") (pinfunction "PB6(XTAL1/TOSC1/PCINT6)_9") (pintype "bidirectional"))
      (node (ref "Q1") (pin "2") (pinfunction "2_2") (pintype "passive"))
    )
    (net (code "97") (name "Net-(IC11-PB7(XTAL2{slash}TOSC2{slash}PCINT7))") (class "Default")
      (node (ref "C38") (pin "2") (pinfunction "2_2") (pintype "passive"))
      (node (ref "IC11") (pin "10") (pinfunction "PB7(XTAL2/TOSC2/PCINT7)_10") (pintype "bidirectional"))
      (node (ref "Q1") (pin "1") (pinfunction "1_1") (pintype "passive"))
    )
    (net (code "98") (name "Net-(JP1-Pad2)") (class "Default")
      (node (ref "JP1") (pin "2") (pinfunction "2_2") (pintype "passive"))
      (node (ref "R1") (pin "2") (pinfunction "2_2") (pintype "passive"))
      (node (ref "R2") (pin "1") (pinfunction "1_1") (pintype "passive"))
    )
    (net (code "99") (name "Net-(JP2-Pad2)") (class "Default")
      (node (ref "JP2") (pin "2") (pinfunction "2_2") (pintype "passive"))
      (node (ref "R3") (pin "2") (pinfunction "2_2") (pintype "passive"))
      (node (ref "R4") (pin "1") (pinfunction "1_1") (pintype "passive"))
    )
    (net (code "100") (name "Net-(JP3-Pad2)") (class "Default")
      (node (ref "JP3") (pin "2") (pinfunction "2_2") (pintype "passive"))
      (node (ref "R5") (pin "2") (pinfunction "2_2") (pintype "passive"))
      (node (ref "R6") (pin "1") (pinfunction "1_1") (pintype "passive"))
    )
    (net (code "101") (name "Net-(JP4-Pad2)") (class "Default")
      (node (ref "JP4") (pin "2") (pinfunction "2_2") (pintype "passive"))
      (node (ref "R7") (pin "2") (pinfunction "2_2") (pintype "passive"))
      (node (ref "R8") (pin "1") (pinfunction "1_1") (pintype "passive"))
    )
    (net (code "102") (name "Net-(JP5-Pad2)") (class "Default")
      (node (ref "JP5") (pin "2") (pinfunction "2_2") (pintype "passive"))
      (node (ref "R10") (pin "1") (pinfunction "1_1") (pintype "passive"))
      (node (ref "R9") (pin "2") (pinfunction "2_2") (pintype "passive"))
    )
    (net (code "103") (name "Net-(JP6-Pad2)") (class "Default")
      (node (ref "JP6") (pin "2") (pinfunction "2_2") (pintype "passive"))
      (node (ref "R11") (pin "2") (pinfunction "2_2") (pintype "passive"))
      (node (ref "R12") (pin "1") (pinfunction "1_1") (pintype "passive"))
    )
    (net (code "104") (name "Net-(JP7-Pad2)") (class "Default")
      (node (ref "JP7") (pin "2") (pinfunction "2_2") (pintype "passive"))
      (node (ref "R13") (pin "2") (pinfunction "2_2") (pintype "passive"))
      (node (ref "R14") (pin "1") (pinfunction "1_1") (pintype "passive"))
    )
    (net (code "105") (name "Net-(JP8-Pad2)") (class "Default")
      (node (ref "JP8") (pin "2") (pinfunction "2_2") (pintype "passive"))
      (node (ref "R15") (pin "2") (pinfunction "2_2") (pintype "passive"))
      (node (ref "R16") (pin "1") (pinfunction "1_1") (pintype "passive"))
    )
    (net (code "106") (name "Net-(JP9-Pad2)") (class "Default")
      (node (ref "JP9") (pin "2") (pinfunction "2_2") (pintype "passive"))
      (node (ref "R17") (pin "2") (pinfunction "2_2") (pintype "passive"))
      (node (ref "R18") (pin "1") (pinfunction "1_1") (pintype "passive"))
    )
    (net (code "107") (name "Net-(JP10-Pad2)") (class "Default")
      (node (ref "JP10") (pin "2") (pinfunction "2_2") (pintype "passive"))
      (node (ref "R19") (pin "2") (pinfunction "2_2") (pintype "passive"))
      (node (ref "R20") (pin "1") (pinfunction "1_1") (pintype "passive"))
    )
    (net (code "108") (name "Net-(JP11-Pad2)") (class "Default")
      (node (ref "JP11") (pin "2") (pinfunction "2_2") (pintype "passive"))
      (node (ref "R21") (pin "2") (pinfunction "2_2") (pintype "passive"))
      (node (ref "R22") (pin "1") (pinfunction "1_1") (pintype "passive"))
    )
    (net (code "109") (name "Net-(JP12-Pad2)") (class "Default")
      (node (ref "JP12") (pin "2") (pinfunction "2_2") (pintype "passive"))
      (node (ref "R23") (pin "2") (pinfunction "2_2") (pintype "passive"))
      (node (ref "R24") (pin "1") (pinfunction "1_1") (pintype "passive"))
    )
    (net (code "110") (name "Net-(JP13-Pad2)") (class "Default")
      (node (ref "JP13") (pin "2") (pinfunction "2_2") (pintype "passive"))
      (node (ref "R25") (pin "2") (pinfunction "2_2") (pintype "passive"))
      (node (ref "R26") (pin "1") (pinfunction "1_1") (pintype "passive"))
    )
    (net (code "111") (name "Net-(JP14-Pad2)") (class "Default")
      (node (ref "JP14") (pin "2") (pinfunction "2_2") (pintype "passive"))
      (node (ref "R27") (pin "2") (pinfunction "2_2") (pintype "passive"))
      (node (ref "R28") (pin "1") (pinfunction "1_1") (pintype "passive"))
    )
    (net (code "112") (name "Net-(JP15-Pad2)") (class "Default")
      (node (ref "JP15") (pin "2") (pinfunction "2_2") (pintype "passive"))
      (node (ref "R29") (pin "2") (pinfunction "2_2") (pintype "passive"))
      (node (ref "R30") (pin "1") (pinfunction "1_1") (pintype "passive"))
    )
    (net (code "113") (name "Net-(JP16-Pad2)") (class "Default")
      (node (ref "JP16") (pin "2") (pinfunction "2_2") (pintype "passive"))
      (node (ref "R31") (pin "2") (pinfunction "2_2") (pintype "passive"))
      (node (ref "R32") (pin "1") (pinfunction "1_1") (pintype "passive"))
    )
    (net (code "114") (name "Net-(JP17-Pad2)") (class "Default")
      (node (ref "JP17") (pin "2") (pinfunction "2_2") (pintype "passive"))
      (node (ref "R33") (pin "2") (pinfunction "2_2") (pintype "passive"))
      (node (ref "R34") (pin "1") (pinfunction "1_1") (pintype "passive"))
    )
    (net (code "115") (name "Net-(JP18-Pad2)") (class "Default")
      (node (ref "JP18") (pin "2") (pinfunction "2_2") (pintype "passive"))
      (node (ref "R35") (pin "2") (pinfunction "2_2") (pintype "passive"))
      (node (ref "R36") (pin "1") (pinfunction "1_1") (pintype "passive"))
    )
    (net (code "116") (name "Net-(JP19-Pad2)") (class "Default")
      (node (ref "JP19") (pin "2") (pinfunction "2_2") (pintype "passive"))
      (node (ref "R37") (pin "2") (pinfunction "2_2") (pintype "passive"))
      (node (ref "R38") (pin "1") (pinfunction "1_1") (pintype "passive"))
    )
    (net (code "117") (name "Net-(JP20-Pad2)") (class "Default")
      (node (ref "JP20") (pin "2") (pinfunction "2_2") (pintype "passive"))
      (node (ref "R39") (pin "2") (pinfunction "2_2") (pintype "passive"))
      (node (ref "R40") (pin "1") (pinfunction "1_1") (pintype "passive"))
    )
    (net (code "118") (name "Net-(JP21-Pad2)") (class "Default")
      (node (ref "JP21") (pin "2") (pinfunction "2_2") (pintype "passive"))
      (node (ref "R41") (pin "2") (pinfunction "2_2") (pintype "passive"))
      (node (ref "R42") (pin "1") (pinfunction "1_1") (pintype "passive"))
    )
    (net (code "119") (name "Net-(JP22-Pad2)") (class "Default")
      (node (ref "JP22") (pin "2") (pinfunction "2_2") (pintype "passive"))
      (node (ref "R43") (pin "2") (pinfunction "2_2") (pintype "passive"))
      (node (ref "R44") (pin "1") (pinfunction "1_1") (pintype "passive"))
    )
    (net (code "120") (name "Net-(JP23-Pad2)") (class "Default")
      (node (ref "JP23") (pin "2") (pinfunction "2_2") (pintype "passive"))
      (node (ref "R45") (pin "2") (pinfunction "2_2") (pintype "passive"))
      (node (ref "R46") (pin "1") (pinfunction "1_1") (pintype "passive"))
    )
    (net (code "121") (name "Net-(JP24-Pad2)") (class "Default")
      (node (ref "JP24") (pin "2") (pinfunction "2_2") (pintype "passive"))
      (node (ref "R47") (pin "2") (pinfunction "2_2") (pintype "passive"))
      (node (ref "R48") (pin "1") (pinfunction "1_1") (pintype "passive"))
    )
    (net (code "122") (name "Net-(JP25-Pad2)") (class "Default")
      (node (ref "JP25") (pin "2") (pinfunction "2_2") (pintype "passive"))
      (node (ref "R49") (pin "2") (pinfunction "2_2") (pintype "passive"))
      (node (ref "R50") (pin "1") (pinfunction "1_1") (pintype "passive"))
    )
    (net (code "123") (name "Net-(JP26-Pad2)") (class "Default")
      (node (ref "JP26") (pin "2") (pinfunction "2_2") (pintype "passive"))
      (node (ref "R51") (pin "2") (pinfunction "2_2") (pintype "passive"))
      (node (ref "R52") (pin "1") (pinfunction "1_1") (pintype "passive"))
    )
    (net (code "124") (name "Net-(JP27-Pad2)") (class "Default")
      (node (ref "JP27") (pin "2") (pinfunction "2_2") (pintype "passive"))
      (node (ref "R53") (pin "2") (pinfunction "2_2") (pintype "passive"))
      (node (ref "R54") (pin "1") (pinfunction "1_1") (pintype "passive"))
    )
    (net (code "125") (name "Net-(JP28-Pad2)") (class "Default")
      (node (ref "JP28") (pin "2") (pinfunction "2_2") (pintype "passive"))
      (node (ref "R55") (pin "2") (pinfunction "2_2") (pintype "passive"))
      (node (ref "R56") (pin "1") (pinfunction "1_1") (pintype "passive"))
    )
    (net (code "126") (name "Net-(JP29-Pad2)") (class "Default")
      (node (ref "JP29") (pin "2") (pinfunction "2_2") (pintype "passive"))
      (node (ref "R57") (pin "2") (pinfunction "2_2") (pintype "passive"))
      (node (ref "R58") (pin "1") (pinfunction "1_1") (pintype "passive"))
    )
    (net (code "127") (name "Net-(JP30-Pad2)") (class "Default")
      (node (ref "JP30") (pin "2") (pinfunction "2_2") (pintype "passive"))
      (node (ref "R59") (pin "2") (pinfunction "2_2") (pintype "passive"))
      (node (ref "R60") (pin "1") (pinfunction "1_1") (pintype "passive"))
    )
    (net (code "128") (name "Net-(JP31-Pad2)") (class "Default")
      (node (ref "JP31") (pin "2") (pinfunction "2_2") (pintype "passive"))
      (node (ref "R61") (pin "2") (pinfunction "2_2") (pintype "passive"))
      (node (ref "R62") (pin "1") (pinfunction "1_1") (pintype "passive"))
    )
    (net (code "129") (name "Net-(JP32-Pad2)") (class "Default")
      (node (ref "JP32") (pin "2") (pinfunction "2_2") (pintype "passive"))
      (node (ref "R63") (pin "2") (pinfunction "2_2") (pintype "passive"))
      (node (ref "R64") (pin "1") (pinfunction "1_1") (pintype "passive"))
    )
    (net (code "130") (name "Net-(JP33-Pad2)") (class "Default")
      (node (ref "JP33") (pin "2") (pinfunction "2_2") (pintype "passive"))
      (node (ref "R65") (pin "2") (pinfunction "2_2") (pintype "passive"))
      (node (ref "R66") (pin "1") (pinfunction "1_1") (pintype "passive"))
    )
    (net (code "131") (name "Net-(JP34-Pad2)") (class "Default")
      (node (ref "JP34") (pin "2") (pinfunction "2_2") (pintype "passive"))
      (node (ref "R67") (pin "2") (pinfunction "2_2") (pintype "passive"))
      (node (ref "R68") (pin "1") (pinfunction "1_1") (pintype "passive"))
    )
    (net (code "132") (name "Net-(JP35-Pad2)") (class "Default")
      (node (ref "JP35") (pin "2") (pinfunction "2_2") (pintype "passive"))
      (node (ref "R69") (pin "2") (pinfunction "2_2") (pintype "passive"))
      (node (ref "R70") (pin "1") (pinfunction "1_1") (pintype "passive"))
    )
    (net (code "133") (name "Net-(JP36-Pad2)") (class "Default")
      (node (ref "JP36") (pin "2") (pinfunction "2_2") (pintype "passive"))
      (node (ref "R71") (pin "2") (pinfunction "2_2") (pintype "passive"))
      (node (ref "R72") (pin "1") (pinfunction "1_1") (pintype "passive"))
    )
    (net (code "134") (name "Net-(LED1-PadA)") (class "Default")
      (node (ref "LED1") (pin "A") (pinfunction "A_A") (pintype "passive"))
      (node (ref "R74") (pin "1") (pinfunction "1_1") (pintype "passive"))
    )
    (net (code "135") (name "VCC") (class "Default")
      (node (ref "C37") (pin "1") (pinfunction "1_1") (pintype "passive"))
      (node (ref "EXTEND") (pin "4") (pinfunction "4_4") (pintype "passive"))
      (node (ref "IC1") (pin "14") (pinfunction "VCC_14") (pintype "power_in"))
      (node (ref "IC10") (pin "16") (pinfunction "VCC_16") (pintype "power_in"))
      (node (ref "IC11") (pin "20") (pinfunction "AVCC_20") (pintype "passive"))
      (node (ref "IC11") (pin "21") (pinfunction "AREF_21") (pintype "passive"))
      (node (ref "IC11") (pin "7") (pinfunction "VCC_7") (pintype "power_in"))
      (node (ref "IC2") (pin "14") (pinfunction "VCC_14") (pintype "power_in"))
      (node (ref "IC3") (pin "14") (pinfunction "VCC_14") (pintype "power_in"))
      (node (ref "IC4") (pin "14") (pinfunction "VCC_14") (pintype "power_in"))
      (node (ref "IC5") (pin "14") (pinfunction "VCC_14") (pintype "power_in"))
      (node (ref "IC6") (pin "14") (pinfunction "VCC_14") (pintype "power_in"))
      (node (ref "IC7") (pin "16") (pinfunction "VCC_16") (pintype "power_in"))
      (node (ref "IC8") (pin "16") (pinfunction "VCC_16") (pintype "power_in"))
      (node (ref "IC9") (pin "16") (pinfunction "VCC_16") (pintype "power_in"))
      (node (ref "ISP") (pin "2") (pinfunction "2_2") (pintype "passive"))
      (node (ref "JRX") (pin "2") (pinfunction "2_2") (pintype "passive"))
      (node (ref "JRY") (pin "2") (pinfunction "2_2") (pintype "passive"))
      (node (ref "JRZ") (pin "2") (pinfunction "2_2") (pintype "passive"))
      (node (ref "JX") (pin "2") (pinfunction "2_2") (pintype "passive"))
      (node (ref "JY") (pin "2") (pinfunction "2_2") (pintype "passive"))
      (node (ref "JZ") (pin "2") (pinfunction "2_2") (pintype "passive"))
      (node (ref "LED2") (pin "A") (pinfunction "A_A") (pintype "passive"))
      (node (ref "R1") (pin "1") (pinfunction "1_1") (pintype "passive"))
      (node (ref "R11") (pin "1") (pinfunction "1_1") (pintype "passive"))
      (node (ref "R13") (pin "1") (pinfunction "1_1") (pintype "passive"))
      (node (ref "R15") (pin "1") (pinfunction "1_1") (pintype "passive"))
      (node (ref "R17") (pin "1") (pinfunction "1_1") (pintype "passive"))
      (node (ref "R19") (pin "1") (pinfunction "1_1") (pintype "passive"))
      (node (ref "R21") (pin "1") (pinfunction "1_1") (pintype "passive"))
      (node (ref "R23") (pin "1") (pinfunction "1_1") (pintype "passive"))
      (node (ref "R25") (pin "1") (pinfunction "1_1") (pintype "passive"))
      (node (ref "R27") (pin "1") (pinfunction "1_1") (pintype "passive"))
      (node (ref "R29") (pin "1") (pinfunction "1_1") (pintype "passive"))
      (node (ref "R3") (pin "1") (pinfunction "1_1") (pintype "passive"))
      (node (ref "R31") (pin "1") (pinfunction "1_1") (pintype "passive"))
      (node (ref "R33") (pin "1") (pinfunction "1_1") (pintype "passive"))
      (node (ref "R35") (pin "1") (pinfunction "1_1") (pintype "passive"))
      (node (ref "R37") (pin "1") (pinfunction "1_1") (pintype "passive"))
      (node (ref "R39") (pin "1") (pinfunction "1_1") (pintype "passive"))
      (node (ref "R41") (pin "1") (pinfunction "1_1") (pintype "passive"))
      (node (ref "R43") (pin "1") (pinfunction "1_1") (pintype "passive"))
      (node (ref "R45") (pin "1") (pinfunction "1_1") (pintype "passive"))
      (node (ref "R47") (pin "1") (pinfunction "1_1") (pintype "passive"))
      (node (ref "R49") (pin "1") (pinfunction "1_1") (pintype "passive"))
      (node (ref "R5") (pin "1") (pinfunction "1_1") (pintype "passive"))
      (node (ref "R51") (pin "1") (pinfunction "1_1") (pintype "passive"))
      (node (ref "R53") (pin "1") (pinfunction "1_1") (pintype "passive"))
      (node (ref "R55") (pin "1") (pinfunction "1_1") (pintype "passive"))
      (node (ref "R57") (pin "1") (pinfunction "1_1") (pintype "passive"))
      (node (ref "R59") (pin "1") (pinfunction "1_1") (pintype "passive"))
      (node (ref "R61") (pin "1") (pinfunction "1_1") (pintype "passive"))
      (node (ref "R63") (pin "1") (pinfunction "1_1") (pintype "passive"))
      (node (ref "R65") (pin "1") (pinfunction "1_1") (pintype "passive"))
      (node (ref "R67") (pin "1") (pinfunction "1_1") (pintype "passive"))
      (node (ref "R69") (pin "1") (pinfunction "1_1") (pintype "passive"))
      (node (ref "R7") (pin "1") (pinfunction "1_1") (pintype "passive"))
      (node (ref "R71") (pin "1") (pinfunction "1_1") (pintype "passive"))
      (node (ref "R73") (pin "1") (pinfunction "1_1") (pintype "passive"))
      (node (ref "R75") (pin "1") (pinfunction "1_1") (pintype "passive"))
      (node (ref "R9") (pin "1") (pinfunction "1_1") (pintype "passive"))
    )
    (net (code "136") (name "unconnected-(IC7A-~{QH}-Pad7)") (class "Default")
      (node (ref "IC7") (pin "7") (pinfunction "~{QH}_7") (pintype "output"))
    )
    (net (code "137") (name "unconnected-(IC8A-~{QH}-Pad7)") (class "Default")
      (node (ref "IC8") (pin "7") (pinfunction "~{QH}_7") (pintype "output"))
    )
    (net (code "138") (name "unconnected-(IC9A-~{QH}-Pad7)") (class "Default")
      (node (ref "IC9") (pin "7") (pinfunction "~{QH}_7") (pintype "output"))
    )
    (net (code "139") (name "unconnected-(IC10A-~{QH}-Pad7)") (class "Default")
      (node (ref "IC10") (pin "7") (pinfunction "~{QH}_7") (pintype "output"))
    )
    (net (code "140") (name "unconnected-(IC11-PD0(RXD{slash}PCINT16)-Pad2)") (class "Default")
      (node (ref "IC11") (pin "2") (pinfunction "PD0(RXD/PCINT16)_2") (pintype "bidirectional"))
    )
    (net (code "141") (name "unconnected-(IC11-PD1(TXD{slash}PCINT17)-Pad3)") (class "Default")
      (node (ref "IC11") (pin "3") (pinfunction "PD1(TXD/PCINT17)_3") (pintype "bidirectional"))
    )
  )
)
